# Breakout_Connector.net
KiCad netlist of a schematic drawn in Altium Designer
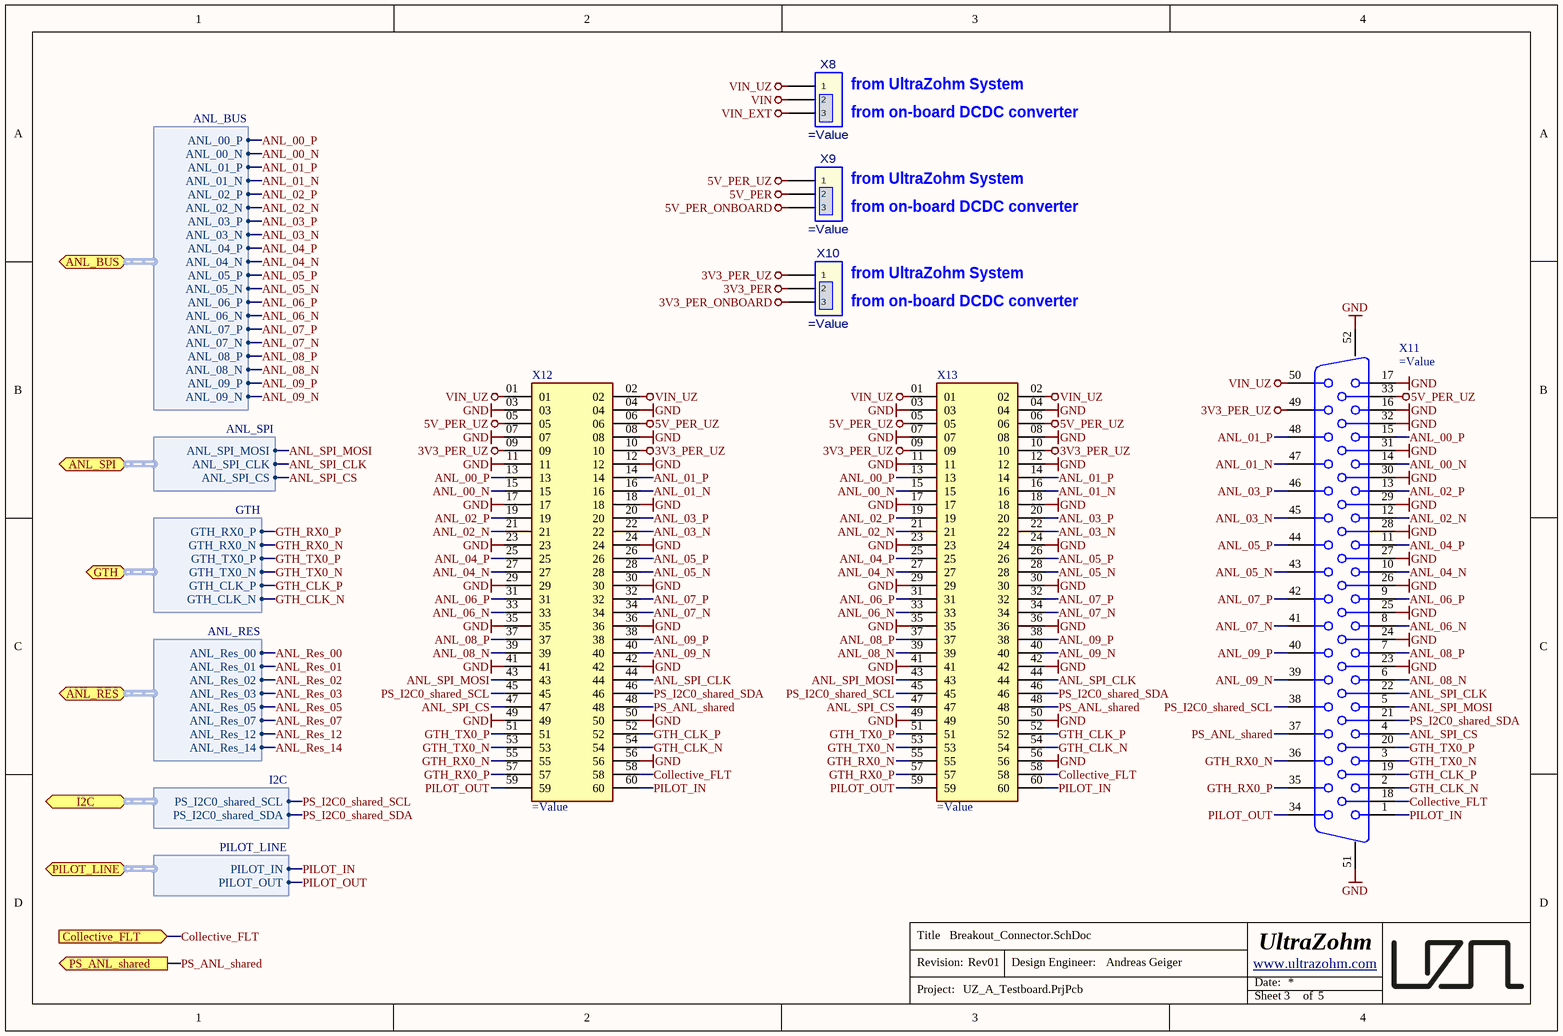
[diagram p0: Breakout_Connector.SchDoc]

(export (version "E")
  (design (tool "Eeschema 10.0.6"))
  (components
    (comp (ref "X8")
      (value "~")
      (footprint "TSW-103-XX-XXX-S")
      (description ".025[0.64] SQ. POST TERMINAL STRIP ASSEMBLY.")
      (fields
        (field (name "MANUFACTURER") "SAMTEC")
        (field (name "MPN") "TSW-103-07-F-S")
        (field (name "CREATED") "2020_11_26_AGeiger")
      )
      (libsource (lib "UZ_A_Testboard") (part "TSW-103-XX-XXX-S"))
    )
    (comp (ref "X9")
      (value "~")
      (footprint "TSW-103-XX-XXX-S")
      (description ".025[0.64] SQ. POST TERMINAL STRIP ASSEMBLY.")
      (fields
        (field (name "MANUFACTURER") "SAMTEC")
        (field (name "MPN") "TSW-103-07-F-S")
        (field (name "CREATED") "2020_11_26_AGeiger")
      )
      (libsource (lib "UZ_A_Testboard") (part "TSW-103-XX-XXX-S"))
    )
    (comp (ref "X10")
      (value "~")
      (footprint "TSW-103-XX-XXX-S")
      (description ".025[0.64] SQ. POST TERMINAL STRIP ASSEMBLY.")
      (fields
        (field (name "MANUFACTURER") "SAMTEC")
        (field (name "MPN") "TSW-103-07-F-S")
        (field (name "CREATED") "2020_11_26_AGeiger")
      )
      (libsource (lib "UZ_A_Testboard") (part "TSW-103-XX-XXX-S"))
    )
    (comp (ref "X11")
      (value "~")
      (footprint "dsub50_female_164A18759X")
      (description "D-SUB, female, right angle, 50pos, 9.4mm pitch")
      (fields
        (field (name "MF") "CONEC")
        (field (name "MPN") "164A18759X")
        (field (name "CREATED") "2019_10_24_AGeiger")
      )
      (libsource (lib "UZ_A_Testboard") (part "DSUB50_female"))
    )
    (comp (ref "X12")
      (value "~")
      (footprint "TSM-130-01-F-DV")
      (fields
        (field (name "MF") "Samtec")
        (field (name "MPN") "TSM-130-01-F-DV")
        (field (name "CREATED") "2021_03_23_AGeiger")
      )
      (libsource (lib "UZ_A_Testboard") (part "TSM-130-01-F-DV"))
    )
    (comp (ref "X13")
      (value "~")
      (footprint "HTSS-130-01-L-DV")
      (fields (field (name "MF") "SAMTEC") (field (name "MPN") "HTSS-130-01-L-DV"))
      (libsource (lib "UZ_A_Testboard") (part "HTSS-130-01-L-DV"))
    )
  )
  (nets
    (net (code "8") (name "/ANL_00_N") (class "Default")
      (node (ref "X11") (pin "14") (pinfunction "14_14") (pintype "passive"))
      (node (ref "X12") (pin "15") (pinfunction "15_15") (pintype "passive"))
      (node (ref "X13") (pin "15") (pinfunction "15_15") (pintype "passive"))
    )
    (net (code "9") (name "/ANL_00_P") (class "Default")
      (node (ref "X11") (pin "15") (pinfunction "15_15") (pintype "passive"))
      (node (ref "X12") (pin "13") (pinfunction "13_13") (pintype "passive"))
      (node (ref "X13") (pin "13") (pinfunction "13_13") (pintype "passive"))
    )
    (net (code "10") (name "/ANL_01_N") (class "Default")
      (node (ref "X11") (pin "47") (pinfunction "47_47") (pintype "passive"))
      (node (ref "X12") (pin "16") (pinfunction "16_16") (pintype "passive"))
      (node (ref "X13") (pin "16") (pinfunction "16_16") (pintype "passive"))
    )
    (net (code "11") (name "/ANL_01_P") (class "Default")
      (node (ref "X11") (pin "48") (pinfunction "48_48") (pintype "passive"))
      (node (ref "X12") (pin "14") (pinfunction "14_14") (pintype "passive"))
      (node (ref "X13") (pin "14") (pinfunction "14_14") (pintype "passive"))
    )
    (net (code "12") (name "/ANL_02_N") (class "Default")
      (node (ref "X11") (pin "12") (pinfunction "12_12") (pintype "passive"))
      (node (ref "X12") (pin "21") (pinfunction "21_21") (pintype "passive"))
      (node (ref "X13") (pin "21") (pinfunction "21_21") (pintype "passive"))
    )
    (net (code "13") (name "/ANL_02_P") (class "Default")
      (node (ref "X11") (pin "13") (pinfunction "13_13") (pintype "passive"))
      (node (ref "X12") (pin "19") (pinfunction "19_19") (pintype "passive"))
      (node (ref "X13") (pin "19") (pinfunction "19_19") (pintype "passive"))
    )
    (net (code "14") (name "/ANL_03_N") (class "Default")
      (node (ref "X11") (pin "45") (pinfunction "45_45") (pintype "passive"))
      (node (ref "X12") (pin "22") (pinfunction "22_22") (pintype "passive"))
      (node (ref "X13") (pin "22") (pinfunction "22_22") (pintype "passive"))
    )
    (net (code "15") (name "/ANL_03_P") (class "Default")
      (node (ref "X11") (pin "46") (pinfunction "46_46") (pintype "passive"))
      (node (ref "X12") (pin "20") (pinfunction "20_20") (pintype "passive"))
      (node (ref "X13") (pin "20") (pinfunction "20_20") (pintype "passive"))
    )
    (net (code "16") (name "/ANL_04_N") (class "Default")
      (node (ref "X11") (pin "10") (pinfunction "10_10") (pintype "passive"))
      (node (ref "X12") (pin "27") (pinfunction "27_27") (pintype "passive"))
      (node (ref "X13") (pin "27") (pinfunction "27_27") (pintype "passive"))
    )
    (net (code "17") (name "/ANL_04_P") (class "Default")
      (node (ref "X11") (pin "11") (pinfunction "11_11") (pintype "passive"))
      (node (ref "X12") (pin "25") (pinfunction "25_25") (pintype "passive"))
      (node (ref "X13") (pin "25") (pinfunction "25_25") (pintype "passive"))
    )
    (net (code "18") (name "/ANL_05_N") (class "Default")
      (node (ref "X11") (pin "43") (pinfunction "43_43") (pintype "passive"))
      (node (ref "X12") (pin "28") (pinfunction "28_28") (pintype "passive"))
      (node (ref "X13") (pin "28") (pinfunction "28_28") (pintype "passive"))
    )
    (net (code "19") (name "/ANL_05_P") (class "Default")
      (node (ref "X11") (pin "44") (pinfunction "44_44") (pintype "passive"))
      (node (ref "X12") (pin "26") (pinfunction "26_26") (pintype "passive"))
      (node (ref "X13") (pin "26") (pinfunction "26_26") (pintype "passive"))
    )
    (net (code "20") (name "/ANL_06_N") (class "Default")
      (node (ref "X11") (pin "8") (pinfunction "8_8") (pintype "passive"))
      (node (ref "X12") (pin "33") (pinfunction "33_33") (pintype "passive"))
      (node (ref "X13") (pin "33") (pinfunction "33_33") (pintype "passive"))
    )
    (net (code "21") (name "/ANL_06_P") (class "Default")
      (node (ref "X11") (pin "9") (pinfunction "9_9") (pintype "passive"))
      (node (ref "X12") (pin "31") (pinfunction "31_31") (pintype "passive"))
      (node (ref "X13") (pin "31") (pinfunction "31_31") (pintype "passive"))
    )
    (net (code "22") (name "/ANL_07_N") (class "Default")
      (node (ref "X11") (pin "41") (pinfunction "41_41") (pintype "passive"))
      (node (ref "X12") (pin "34") (pinfunction "34_34") (pintype "passive"))
      (node (ref "X13") (pin "34") (pinfunction "34_34") (pintype "passive"))
    )
    (net (code "23") (name "/ANL_07_P") (class "Default")
      (node (ref "X11") (pin "42") (pinfunction "42_42") (pintype "passive"))
      (node (ref "X12") (pin "32") (pinfunction "32_32") (pintype "passive"))
      (node (ref "X13") (pin "32") (pinfunction "32_32") (pintype "passive"))
    )
    (net (code "24") (name "/ANL_08_N") (class "Default")
      (node (ref "X11") (pin "6") (pinfunction "6_6") (pintype "passive"))
      (node (ref "X12") (pin "39") (pinfunction "39_39") (pintype "passive"))
      (node (ref "X13") (pin "39") (pinfunction "39_39") (pintype "passive"))
    )
    (net (code "25") (name "/ANL_08_P") (class "Default")
      (node (ref "X11") (pin "7") (pinfunction "7_7") (pintype "passive"))
      (node (ref "X12") (pin "37") (pinfunction "37_37") (pintype "passive"))
      (node (ref "X13") (pin "37") (pinfunction "37_37") (pintype "passive"))
    )
    (net (code "26") (name "/ANL_09_N") (class "Default")
      (node (ref "X11") (pin "39") (pinfunction "39_39") (pintype "passive"))
      (node (ref "X12") (pin "40") (pinfunction "40_40") (pintype "passive"))
      (node (ref "X13") (pin "40") (pinfunction "40_40") (pintype "passive"))
    )
    (net (code "27") (name "/ANL_09_P") (class "Default")
      (node (ref "X11") (pin "40") (pinfunction "40_40") (pintype "passive"))
      (node (ref "X12") (pin "38") (pinfunction "38_38") (pintype "passive"))
      (node (ref "X13") (pin "38") (pinfunction "38_38") (pintype "passive"))
    )
    (net (code "36") (name "/ANL_SPI_CLK") (class "Default")
      (node (ref "X11") (pin "22") (pinfunction "22_22") (pintype "passive"))
      (node (ref "X12") (pin "44") (pinfunction "44_44") (pintype "passive"))
      (node (ref "X13") (pin "44") (pinfunction "44_44") (pintype "passive"))
    )
    (net (code "37") (name "/ANL_SPI_CS") (class "Default")
      (node (ref "X11") (pin "4") (pinfunction "4_4") (pintype "passive"))
      (node (ref "X12") (pin "47") (pinfunction "47_47") (pintype "passive"))
      (node (ref "X13") (pin "47") (pinfunction "47_47") (pintype "passive"))
    )
    (net (code "38") (name "/ANL_SPI_MOSI") (class "Default")
      (node (ref "X11") (pin "5") (pinfunction "5_5") (pintype "passive"))
      (node (ref "X12") (pin "43") (pinfunction "43_43") (pintype "passive"))
      (node (ref "X13") (pin "43") (pinfunction "43_43") (pintype "passive"))
    )
    (net (code "39") (name "/Collective_FLT") (class "Default")
      (node (ref "X11") (pin "18") (pinfunction "18_18") (pintype "passive"))
      (node (ref "X12") (pin "58") (pinfunction "58_58") (pintype "passive"))
      (node (ref "X13") (pin "58") (pinfunction "58_58") (pintype "passive"))
    )
    (net (code "40") (name "/GTH_CLK_N") (class "Default")
      (node (ref "X11") (pin "2") (pinfunction "2_2") (pintype "passive"))
      (node (ref "X12") (pin "54") (pinfunction "54_54") (pintype "passive"))
      (node (ref "X13") (pin "54") (pinfunction "54_54") (pintype "passive"))
    )
    (net (code "41") (name "/GTH_CLK_P") (class "Default")
      (node (ref "X11") (pin "19") (pinfunction "19_19") (pintype "passive"))
      (node (ref "X12") (pin "52") (pinfunction "52_52") (pintype "passive"))
      (node (ref "X13") (pin "52") (pinfunction "52_52") (pintype "passive"))
    )
    (net (code "42") (name "/GTH_RX0_N") (class "Default")
      (node (ref "X11") (pin "36") (pinfunction "36_36") (pintype "passive"))
      (node (ref "X12") (pin "55") (pinfunction "55_55") (pintype "passive"))
      (node (ref "X13") (pin "55") (pinfunction "55_55") (pintype "passive"))
    )
    (net (code "43") (name "/GTH_RX0_P") (class "Default")
      (node (ref "X11") (pin "35") (pinfunction "35_35") (pintype "passive"))
      (node (ref "X12") (pin "57") (pinfunction "57_57") (pintype "passive"))
      (node (ref "X13") (pin "57") (pinfunction "57_57") (pintype "passive"))
    )
    (net (code "44") (name "/GTH_TX0_N") (class "Default")
      (node (ref "X11") (pin "3") (pinfunction "3_3") (pintype "passive"))
      (node (ref "X12") (pin "53") (pinfunction "53_53") (pintype "passive"))
      (node (ref "X13") (pin "53") (pinfunction "53_53") (pintype "passive"))
    )
    (net (code "45") (name "/GTH_TX0_P") (class "Default")
      (node (ref "X11") (pin "20") (pinfunction "20_20") (pintype "passive"))
      (node (ref "X12") (pin "51") (pinfunction "51_51") (pintype "passive"))
      (node (ref "X13") (pin "51") (pinfunction "51_51") (pintype "passive"))
    )
    (net (code "46") (name "/PILOT_IN") (class "Default")
      (node (ref "X11") (pin "1") (pinfunction "1_1") (pintype "passive"))
      (node (ref "X12") (pin "60") (pinfunction "60_60") (pintype "passive"))
      (node (ref "X13") (pin "60") (pinfunction "60_60") (pintype "passive"))
    )
    (net (code "47") (name "/PILOT_OUT") (class "Default")
      (node (ref "X11") (pin "34") (pinfunction "34_34") (pintype "passive"))
      (node (ref "X12") (pin "59") (pinfunction "59_59") (pintype "passive"))
      (node (ref "X13") (pin "59") (pinfunction "59_59") (pintype "passive"))
    )
    (net (code "48") (name "/PS_ANL_shared") (class "Default")
      (node (ref "X11") (pin "37") (pinfunction "37_37") (pintype "passive"))
      (node (ref "X12") (pin "48") (pinfunction "48_48") (pintype "passive"))
      (node (ref "X13") (pin "48") (pinfunction "48_48") (pintype "passive"))
    )
    (net (code "49") (name "/PS_I2C0_shared_SCL") (class "Default")
      (node (ref "X11") (pin "38") (pinfunction "38_38") (pintype "passive"))
      (node (ref "X12") (pin "45") (pinfunction "45_45") (pintype "passive"))
      (node (ref "X13") (pin "45") (pinfunction "45_45") (pintype "passive"))
    )
    (net (code "50") (name "/PS_I2C0_shared_SDA") (class "Default")
      (node (ref "X11") (pin "21") (pinfunction "21_21") (pintype "passive"))
      (node (ref "X12") (pin "46") (pinfunction "46_46") (pintype "passive"))
      (node (ref "X13") (pin "46") (pinfunction "46_46") (pintype "passive"))
    )
    (net (code "57") (name "3V3_PER") (class "Default")
      (node (ref "X10") (pin "2") (pinfunction "2_2") (pintype "passive"))
    )
    (net (code "58") (name "3V3_PER_ONBOARD") (class "Default")
      (node (ref "X10") (pin "3") (pinfunction "3_3") (pintype "passive"))
    )
    (net (code "59") (name "3V3_PER_UZ") (class "Default")
      (node (ref "X10") (pin "1") (pinfunction "1_1") (pintype "passive"))
      (node (ref "X11") (pin "49") (pinfunction "49_49") (pintype "passive"))
      (node (ref "X12") (pin "09") (pinfunction "09_09") (pintype "passive"))
      (node (ref "X12") (pin "10") (pinfunction "10_10") (pintype "passive"))
      (node (ref "X13") (pin "09") (pinfunction "09_09") (pintype "passive"))
      (node (ref "X13") (pin "10") (pinfunction "10_10") (pintype "passive"))
    )
    (net (code "60") (name "5V_PER") (class "Default")
      (node (ref "X9") (pin "2") (pinfunction "2_2") (pintype "passive"))
    )
    (net (code "61") (name "5V_PER_ONBOARD") (class "Default")
      (node (ref "X9") (pin "3") (pinfunction "3_3") (pintype "passive"))
    )
    (net (code "62") (name "5V_PER_UZ") (class "Default")
      (node (ref "X11") (pin "33") (pinfunction "33_33") (pintype "passive"))
      (node (ref "X12") (pin "05") (pinfunction "05_05") (pintype "passive"))
      (node (ref "X12") (pin "06") (pinfunction "06_06") (pintype "passive"))
      (node (ref "X13") (pin "05") (pinfunction "05_05") (pintype "passive"))
      (node (ref "X13") (pin "06") (pinfunction "06_06") (pintype "passive"))
      (node (ref "X9") (pin "1") (pinfunction "1_1") (pintype "passive"))
    )
    (net (code "63") (name "GND") (class "Default")
      (node (ref "X11") (pin "16") (pinfunction "16_16") (pintype "passive"))
      (node (ref "X11") (pin "17") (pinfunction "17_17") (pintype "passive"))
      (node (ref "X11") (pin "23") (pinfunction "23_23") (pintype "passive"))
      (node (ref "X11") (pin "24") (pinfunction "24_24") (pintype "passive"))
      (node (ref "X11") (pin "25") (pinfunction "25_25") (pintype "passive"))
      (node (ref "X11") (pin "26") (pinfunction "26_26") (pintype "passive"))
      (node (ref "X11") (pin "27") (pinfunction "27_27") (pintype "passive"))
      (node (ref "X11") (pin "28") (pinfunction "28_28") (pintype "passive"))
      (node (ref "X11") (pin "29") (pinfunction "29_29") (pintype "passive"))
      (node (ref "X11") (pin "30") (pinfunction "30_30") (pintype "passive"))
      (node (ref "X11") (pin "31") (pinfunction "31_31") (pintype "passive"))
      (node (ref "X11") (pin "32") (pinfunction "32_32") (pintype "passive"))
      (node (ref "X11") (pin "51") (pinfunction "51_51") (pintype "passive"))
      (node (ref "X11") (pin "52") (pinfunction "52_52") (pintype "passive"))
      (node (ref "X12") (pin "03") (pinfunction "03_03") (pintype "passive"))
      (node (ref "X12") (pin "04") (pinfunction "04_04") (pintype "passive"))
      (node (ref "X12") (pin "07") (pinfunction "07_07") (pintype "passive"))
      (node (ref "X12") (pin "08") (pinfunction "08_08") (pintype "passive"))
      (node (ref "X12") (pin "11") (pinfunction "11_11") (pintype "passive"))
      (node (ref "X12") (pin "12") (pinfunction "12_12") (pintype "passive"))
      (node (ref "X12") (pin "17") (pinfunction "17_17") (pintype "passive"))
      (node (ref "X12") (pin "18") (pinfunction "18_18") (pintype "passive"))
      (node (ref "X12") (pin "23") (pinfunction "23_23") (pintype "passive"))
      (node (ref "X12") (pin "24") (pinfunction "24_24") (pintype "passive"))
      (node (ref "X12") (pin "29") (pinfunction "29_29") (pintype "passive"))
      (node (ref "X12") (pin "30") (pinfunction "30_30") (pintype "passive"))
      (node (ref "X12") (pin "35") (pinfunction "35_35") (pintype "passive"))
      (node (ref "X12") (pin "36") (pinfunction "36_36") (pintype "passive"))
      (node (ref "X12") (pin "41") (pinfunction "41_41") (pintype "passive"))
      (node (ref "X12") (pin "42") (pinfunction "42_42") (pintype "passive"))
      (node (ref "X12") (pin "49") (pinfunction "49_49") (pintype "passive"))
      (node (ref "X12") (pin "50") (pinfunction "50_50") (pintype "passive"))
      (node (ref "X12") (pin "56") (pinfunction "56_56") (pintype "passive"))
      (node (ref "X13") (pin "03") (pinfunction "03_03") (pintype "passive"))
      (node (ref "X13") (pin "04") (pinfunction "04_04") (pintype "passive"))
      (node (ref "X13") (pin "07") (pinfunction "07_07") (pintype "passive"))
      (node (ref "X13") (pin "08") (pinfunction "08_08") (pintype "passive"))
      (node (ref "X13") (pin "11") (pinfunction "11_11") (pintype "passive"))
      (node (ref "X13") (pin "12") (pinfunction "12_12") (pintype "passive"))
      (node (ref "X13") (pin "17") (pinfunction "17_17") (pintype "passive"))
      (node (ref "X13") (pin "18") (pinfunction "18_18") (pintype "passive"))
      (node (ref "X13") (pin "23") (pinfunction "23_23") (pintype "passive"))
      (node (ref "X13") (pin "24") (pinfunction "24_24") (pintype "passive"))
      (node (ref "X13") (pin "29") (pinfunction "29_29") (pintype "passive"))
      (node (ref "X13") (pin "30") (pinfunction "30_30") (pintype "passive"))
      (node (ref "X13") (pin "35") (pinfunction "35_35") (pintype "passive"))
      (node (ref "X13") (pin "36") (pinfunction "36_36") (pintype "passive"))
      (node (ref "X13") (pin "41") (pinfunction "41_41") (pintype "passive"))
      (node (ref "X13") (pin "42") (pinfunction "42_42") (pintype "passive"))
      (node (ref "X13") (pin "49") (pinfunction "49_49") (pintype "passive"))
      (node (ref "X13") (pin "50") (pinfunction "50_50") (pintype "passive"))
      (node (ref "X13") (pin "56") (pinfunction "56_56") (pintype "passive"))
    )
    (net (code "64") (name "VIN") (class "Default")
      (node (ref "X8") (pin "2") (pinfunction "2_2") (pintype "passive"))
    )
    (net (code "65") (name "VIN_EXT") (class "Default")
      (node (ref "X8") (pin "3") (pinfunction "3_3") (pintype "passive"))
    )
    (net (code "66") (name "VIN_UZ") (class "Default")
      (node (ref "X11") (pin "50") (pinfunction "50_50") (pintype "passive"))
      (node (ref "X12") (pin "01") (pinfunction "01_01") (pintype "passive"))
      (node (ref "X12") (pin "02") (pinfunction "02_02") (pintype "passive"))
      (node (ref "X13") (pin "01") (pinfunction "01_01") (pintype "passive"))
      (node (ref "X13") (pin "02") (pinfunction "02_02") (pintype "passive"))
      (node (ref "X8") (pin "1") (pinfunction "1_1") (pintype "passive"))
    )
  )
)
